# modified.net
KiCad netlist of a schematic drawn in EAGLE
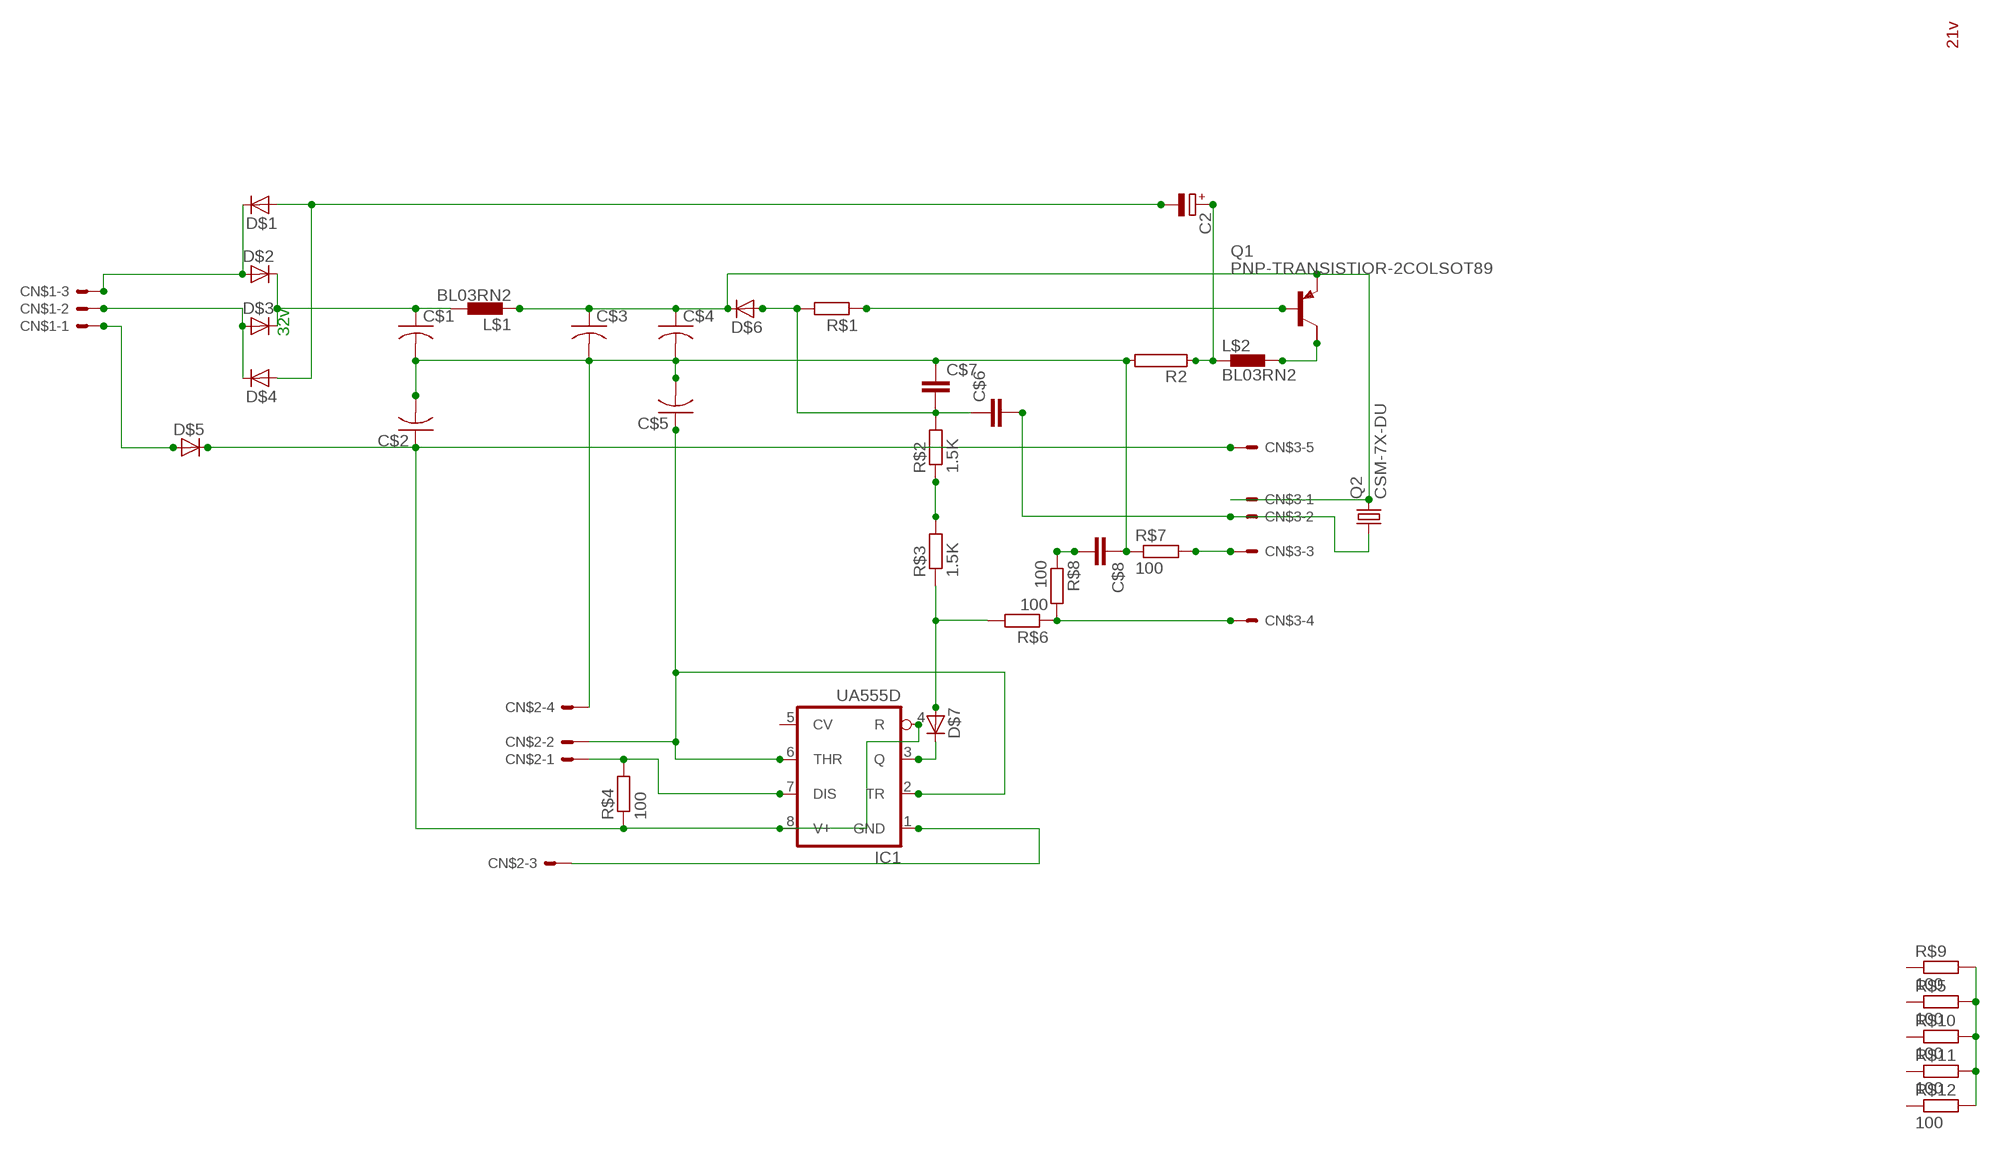
[diagram p0: schematic, sheet 1]

(export (version "E")
  (design (tool "Eeschema 10.0.6"))
  (components
    (comp (ref "C$1")
      (value "C-US050-075X075")
      (footprint "eagle-import:C050-075X075")
      (libsource (lib "eagle-import") (part "C-US050-075X075"))
    )
    (comp (ref "C$2")
      (value "C-US050-075X075")
      (footprint "eagle-import:C050-075X075")
      (libsource (lib "eagle-import") (part "C-US050-075X075"))
    )
    (comp (ref "C$3")
      (value "C-US025-050X050")
      (footprint "eagle-import:C025-050X050")
      (libsource (lib "eagle-import") (part "C-US025-050X050"))
    )
    (comp (ref "C$4")
      (value "C-US025-050X050")
      (footprint "eagle-import:C025-050X050")
      (libsource (lib "eagle-import") (part "C-US025-050X050"))
    )
    (comp (ref "C$5")
      (value "C-US025-050X050")
      (footprint "eagle-import:C025-050X050")
      (libsource (lib "eagle-import") (part "C-US025-050X050"))
    )
    (comp (ref "C$6")
      (value "C7.5/3")
      (footprint "eagle-import:C7.5B3")
      (libsource (lib "eagle-import") (part "C7.5/3"))
    )
    (comp (ref "C$7")
      (value "C7.5/3")
      (footprint "eagle-import:C7.5B3")
      (libsource (lib "eagle-import") (part "C7.5/3"))
    )
    (comp (ref "C$8")
      (value "C2.5/5")
      (footprint "eagle-import:C2.5-5")
      (libsource (lib "eagle-import") (part "C2.5/5"))
    )
    (comp (ref "C2")
      (value "CPOL-EUSANYO_H")
      (footprint "eagle-import:SANYO-OSCON_H")
      (libsource (lib "eagle-import") (part "CPOL-EUSANYO_H"))
    )
    (comp (ref "CN$1")
      (value "KK-156-3")
      (footprint "eagle-import:KK-156-3")
      (libsource (lib "eagle-import") (part "KK-156-3"))
    )
    (comp (ref "CN$2")
      (value "KK-156-4")
      (footprint "eagle-import:KK-156-4")
      (libsource (lib "eagle-import") (part "KK-156-4"))
    )
    (comp (ref "CN$3")
      (value "KK-156-5")
      (footprint "eagle-import:KK-156-5")
      (libsource (lib "eagle-import") (part "KK-156-5"))
    )
    (comp (ref "D$1")
      (value "D-SOD-87")
      (footprint "eagle-import:SOD87")
      (libsource (lib "eagle-import") (part "D-SOD-87"))
    )
    (comp (ref "D$2")
      (value "D-SOD-87")
      (footprint "eagle-import:SOD87")
      (libsource (lib "eagle-import") (part "D-SOD-87"))
    )
    (comp (ref "D$3")
      (value "D-SOD-87")
      (footprint "eagle-import:SOD87")
      (libsource (lib "eagle-import") (part "D-SOD-87"))
    )
    (comp (ref "D$4")
      (value "D-SOD-87")
      (footprint "eagle-import:SOD87")
      (libsource (lib "eagle-import") (part "D-SOD-87"))
    )
    (comp (ref "D$5")
      (value "D-SOD-87")
      (footprint "eagle-import:SOD87")
      (libsource (lib "eagle-import") (part "D-SOD-87"))
    )
    (comp (ref "D$6")
      (value "D-SOD-87")
      (footprint "eagle-import:SOD87")
      (libsource (lib "eagle-import") (part "D-SOD-87"))
    )
    (comp (ref "D$7")
      (value "D-SOD-87")
      (footprint "eagle-import:SOD87")
      (libsource (lib "eagle-import") (part "D-SOD-87"))
    )
    (comp (ref "IC1")
      (value "UA555D")
      (footprint "eagle-import:SO08")
      (libsource (lib "eagle-import") (part "555DUA"))
    )
    (comp (ref "L$1")
      (value "BL03RN2")
      (footprint "eagle-import:BL03RN2")
      (libsource (lib "eagle-import") (part "BL03RN2"))
    )
    (comp (ref "L$2")
      (value "BL03RN2")
      (footprint "eagle-import:BL03RN2")
      (libsource (lib "eagle-import") (part "BL03RN2"))
    )
    (comp (ref "Q1")
      (value "PNP-TRANSISTIOR-2COLSOT89")
      (footprint "eagle-import:SOT89")
      (libsource (lib "eagle-import") (part "PNP-TRANSISTIOR-2COLSOT89"))
    )
    (comp (ref "Q2")
      (value "CSM-7X-DU")
      (footprint "eagle-import:CSM-7X-DU")
      (libsource (lib "eagle-import") (part "CSM-7X-DU"))
    )
    (comp (ref "R$1")
      (value "R-EU_R0603")
      (footprint "eagle-import:R0603")
      (libsource (lib "eagle-import") (part "R-EU_R0603"))
    )
    (comp (ref "R$2")
      (value "1.5K")
      (footprint "eagle-import:R0603")
      (libsource (lib "eagle-import") (part "R-EU_R0603"))
    )
    (comp (ref "R$3")
      (value "1.5K")
      (footprint "eagle-import:R0603")
      (libsource (lib "eagle-import") (part "R-EU_R0603"))
    )
    (comp (ref "R$4")
      (value "100")
      (footprint "eagle-import:R0603")
      (libsource (lib "eagle-import") (part "R-EU_R0603"))
    )
    (comp (ref "R$5")
      (value "100")
      (footprint "eagle-import:R0603")
      (libsource (lib "eagle-import") (part "R-EU_R0603"))
    )
    (comp (ref "R$6")
      (value "100")
      (footprint "eagle-import:R0603")
      (libsource (lib "eagle-import") (part "R-EU_R0603"))
    )
    (comp (ref "R$7")
      (value "100")
      (footprint "eagle-import:R0603")
      (libsource (lib "eagle-import") (part "R-EU_R0603"))
    )
    (comp (ref "R$8")
      (value "100")
      (footprint "eagle-import:R0603")
      (libsource (lib "eagle-import") (part "R-EU_R0603"))
    )
    (comp (ref "R$9")
      (value "100")
      (footprint "eagle-import:R0603")
      (libsource (lib "eagle-import") (part "R-EU_R0603"))
    )
    (comp (ref "R$10")
      (value "100")
      (footprint "eagle-import:R0603")
      (libsource (lib "eagle-import") (part "R-EU_R0603"))
    )
    (comp (ref "R$11")
      (value "100")
      (footprint "eagle-import:R0603")
      (libsource (lib "eagle-import") (part "R-EU_R0603"))
    )
    (comp (ref "R$12")
      (value "100")
      (footprint "eagle-import:R0603")
      (libsource (lib "eagle-import") (part "R-EU_R0603"))
    )
    (comp (ref "R2")
      (value "RAC01")
      (footprint "eagle-import:AC01")
      (libsource (lib "eagle-import") (part "RAC01"))
    )
  )
  (nets
    (net (code "1") (name "Net-(C$8-Pad2)") (class "Default")
      (node (ref "C$8") (pin "2") (pinfunction "2_2") (pintype "passive"))
      (node (ref "R$8") (pin "1") (pinfunction "1_1") (pintype "passive"))
    )
    (net (code "2") (name "Net-(C2-Pad+)") (class "Default")
      (node (ref "C2") (pin "+") (pinfunction "+_+") (pintype "passive"))
      (node (ref "L$2") (pin "1") (pinfunction "1_1") (pintype "passive"))
      (node (ref "R2") (pin "1") (pinfunction "1_1") (pintype "passive"))
    )
    (net (code "3") (name "Net-(CN$1A-S)") (class "Default")
      (node (ref "CN$1") (pin "1") (pinfunction "S_1") (pintype "passive"))
      (node (ref "D$5") (pin "2") (pinfunction "A_2") (pintype "passive"))
    )
    (net (code "4") (name "Net-(CN$1B-S)") (class "Default")
      (node (ref "CN$1") (pin "2") (pinfunction "S_2") (pintype "passive"))
      (node (ref "D$3") (pin "2") (pinfunction "A_2") (pintype "passive"))
      (node (ref "D$4") (pin "1") (pinfunction "C_1") (pintype "passive"))
    )
    (net (code "5") (name "Net-(CN$1C-S)") (class "Default")
      (node (ref "CN$1") (pin "3") (pinfunction "S_3") (pintype "passive"))
      (node (ref "D$1") (pin "1") (pinfunction "C_1") (pintype "passive"))
      (node (ref "D$2") (pin "2") (pinfunction "A_2") (pintype "passive"))
    )
    (net (code "6") (name "Net-(CN$2A-S)") (class "Default")
      (node (ref "CN$2") (pin "1") (pinfunction "S_1") (pintype "passive"))
      (node (ref "IC1") (pin "7") (pinfunction "DIS_7") (pintype "input"))
      (node (ref "R$4") (pin "2") (pinfunction "2_2") (pintype "passive"))
    )
    (net (code "7") (name "Net-(CN$2B-S)") (class "Default")
      (node (ref "C$5") (pin "1") (pinfunction "1_1") (pintype "passive"))
      (node (ref "CN$2") (pin "2") (pinfunction "S_2") (pintype "passive"))
      (node (ref "IC1") (pin "2") (pinfunction "TR_2") (pintype "input"))
      (node (ref "IC1") (pin "6") (pinfunction "THR_6") (pintype "input"))
    )
    (net (code "8") (name "Net-(CN$2C-S)") (class "Default")
      (node (ref "CN$2") (pin "3") (pinfunction "S_3") (pintype "passive"))
      (node (ref "IC1") (pin "1") (pinfunction "GND_1") (pintype "power_in"))
    )
    (net (code "9") (name "Net-(CN$2D-S)") (class "Default")
      (node (ref "C$1") (pin "2") (pinfunction "2_2") (pintype "passive"))
      (node (ref "C$2") (pin "2") (pinfunction "2_2") (pintype "passive"))
      (node (ref "C$3") (pin "2") (pinfunction "2_2") (pintype "passive"))
      (node (ref "C$4") (pin "2") (pinfunction "2_2") (pintype "passive"))
      (node (ref "C$5") (pin "2") (pinfunction "2_2") (pintype "passive"))
      (node (ref "C$7") (pin "1") (pinfunction "1_1") (pintype "passive"))
      (node (ref "C$8") (pin "1") (pinfunction "1_1") (pintype "passive"))
      (node (ref "CN$2") (pin "4") (pinfunction "S_4") (pintype "passive"))
      (node (ref "R$7") (pin "1") (pinfunction "1_1") (pintype "passive"))
      (node (ref "R2") (pin "2") (pinfunction "2_2") (pintype "passive"))
    )
    (net (code "10") (name "Net-(CN$3A-S)") (class "Default")
      (node (ref "C$3") (pin "1") (pinfunction "1_1") (pintype "passive"))
      (node (ref "C$4") (pin "1") (pinfunction "1_1") (pintype "passive"))
      (node (ref "CN$3") (pin "1") (pinfunction "S_1") (pintype "passive"))
      (node (ref "D$6") (pin "1") (pinfunction "C_1") (pintype "passive"))
      (node (ref "L$1") (pin "1") (pinfunction "1_1") (pintype "passive"))
      (node (ref "Q1") (pin "3") (pinfunction "E_3") (pintype "passive"))
      (node (ref "Q2") (pin "2") (pinfunction "2_2") (pintype "passive"))
    )
    (net (code "11") (name "Net-(CN$3B-S)") (class "Default")
      (node (ref "C$6") (pin "2") (pinfunction "2_2") (pintype "passive"))
      (node (ref "CN$3") (pin "2") (pinfunction "S_2") (pintype "passive"))
      (node (ref "Q2") (pin "1") (pinfunction "1_1") (pintype "passive"))
    )
    (net (code "12") (name "Net-(CN$3C-S)") (class "Default")
      (node (ref "CN$3") (pin "3") (pinfunction "S_3") (pintype "passive"))
      (node (ref "R$7") (pin "2") (pinfunction "2_2") (pintype "passive"))
    )
    (net (code "13") (name "Net-(CN$3D-S)") (class "Default")
      (node (ref "CN$3") (pin "4") (pinfunction "S_4") (pintype "passive"))
      (node (ref "R$6") (pin "1") (pinfunction "1_1") (pintype "passive"))
      (node (ref "R$8") (pin "2") (pinfunction "2_2") (pintype "passive"))
    )
    (net (code "14") (name "Net-(CN$3E-S)") (class "Default")
      (node (ref "C$2") (pin "1") (pinfunction "1_1") (pintype "passive"))
      (node (ref "CN$3") (pin "5") (pinfunction "S_5") (pintype "passive"))
      (node (ref "D$5") (pin "1") (pinfunction "C_1") (pintype "passive"))
      (node (ref "IC1") (pin "4") (pinfunction "R_4") (pintype "input"))
      (node (ref "IC1") (pin "8") (pinfunction "V+_8") (pintype "power_in"))
      (node (ref "R$4") (pin "1") (pinfunction "1_1") (pintype "passive"))
    )
    (net (code "15") (name "Net-(D$1-A)") (class "Default")
      (node (ref "C2") (pin "-") (pinfunction "-_-") (pintype "passive"))
      (node (ref "D$1") (pin "2") (pinfunction "A_2") (pintype "passive"))
      (node (ref "D$4") (pin "2") (pinfunction "A_2") (pintype "passive"))
    )
    (net (code "16") (name "Net-(D$2-C)") (class "Default")
      (node (ref "C$1") (pin "1") (pinfunction "1_1") (pintype "passive"))
      (node (ref "D$2") (pin "1") (pinfunction "C_1") (pintype "passive"))
      (node (ref "D$3") (pin "1") (pinfunction "C_1") (pintype "passive"))
      (node (ref "L$1") (pin "2") (pinfunction "2_2") (pintype "passive"))
    )
    (net (code "17") (name "Net-(D$6-A)") (class "Default")
      (node (ref "C$6") (pin "1") (pinfunction "1_1") (pintype "passive"))
      (node (ref "C$7") (pin "2") (pinfunction "2_2") (pintype "passive"))
      (node (ref "D$6") (pin "2") (pinfunction "A_2") (pintype "passive"))
      (node (ref "R$1") (pin "2") (pinfunction "2_2") (pintype "passive"))
      (node (ref "R$2") (pin "2") (pinfunction "2_2") (pintype "passive"))
    )
    (net (code "18") (name "Net-(D$7-A)") (class "Default")
      (node (ref "D$7") (pin "2") (pinfunction "A_2") (pintype "passive"))
      (node (ref "R$3") (pin "1") (pinfunction "1_1") (pintype "passive"))
      (node (ref "R$6") (pin "2") (pinfunction "2_2") (pintype "passive"))
    )
    (net (code "19") (name "Net-(D$7-C)") (class "Default")
      (node (ref "D$7") (pin "1") (pinfunction "C_1") (pintype "passive"))
      (node (ref "IC1") (pin "3") (pinfunction "Q_3") (pintype "output"))
    )
    (net (code "20") (name "Net-(Q1-B)") (class "Default")
      (node (ref "Q1") (pin "1") (pinfunction "B_1") (pintype "passive"))
      (node (ref "R$1") (pin "1") (pinfunction "1_1") (pintype "passive"))
    )
    (net (code "21") (name "Net-(Q1-C)") (class "Default")
      (node (ref "L$2") (pin "2") (pinfunction "2_2") (pintype "passive"))
      (node (ref "Q1") (pin "2") (pinfunction "C_2") (pintype "passive"))
    )
    (net (code "22") (name "Net-(R$2-Pad1)") (class "Default")
      (node (ref "R$2") (pin "1") (pinfunction "1_1") (pintype "passive"))
      (node (ref "R$3") (pin "2") (pinfunction "2_2") (pintype "passive"))
    )
    (net (code "23") (name "Net-(R$10-Pad2)") (class "Default")
      (node (ref "R$10") (pin "2") (pinfunction "2_2") (pintype "passive"))
      (node (ref "R$11") (pin "2") (pinfunction "2_2") (pintype "passive"))
      (node (ref "R$12") (pin "2") (pinfunction "2_2") (pintype "passive"))
      (node (ref "R$5") (pin "2") (pinfunction "2_2") (pintype "passive"))
      (node (ref "R$9") (pin "2") (pinfunction "2_2") (pintype "passive"))
    )
    (net (code "24") (name "unconnected-(IC1-CV-Pad5)") (class "Default")
      (node (ref "IC1") (pin "5") (pinfunction "CV_5") (pintype "input"))
    )
    (net (code "25") (name "unconnected-(Q1-C{slash}-Pad2@1)") (class "Default")
      (node (ref "Q1") (pin "2@1") (pinfunction "C/_2@1") (pintype "passive"))
    )
    (net (code "26") (name "unconnected-(R$5-Pad1)") (class "Default")
      (node (ref "R$5") (pin "1") (pinfunction "1_1") (pintype "passive"))
    )
    (net (code "27") (name "unconnected-(R$9-Pad1)") (class "Default")
      (node (ref "R$9") (pin "1") (pinfunction "1_1") (pintype "passive"))
    )
    (net (code "28") (name "unconnected-(R$10-Pad1)") (class "Default")
      (node (ref "R$10") (pin "1") (pinfunction "1_1") (pintype "passive"))
    )
    (net (code "29") (name "unconnected-(R$11-Pad1)") (class "Default")
      (node (ref "R$11") (pin "1") (pinfunction "1_1") (pintype "passive"))
    )
    (net (code "30") (name "unconnected-(R$12-Pad1)") (class "Default")
      (node (ref "R$12") (pin "1") (pinfunction "1_1") (pintype "passive"))
    )
  )
)
